# rc13-mbed-main-board2.net
KiCad netlist of a schematic drawn in EAGLE
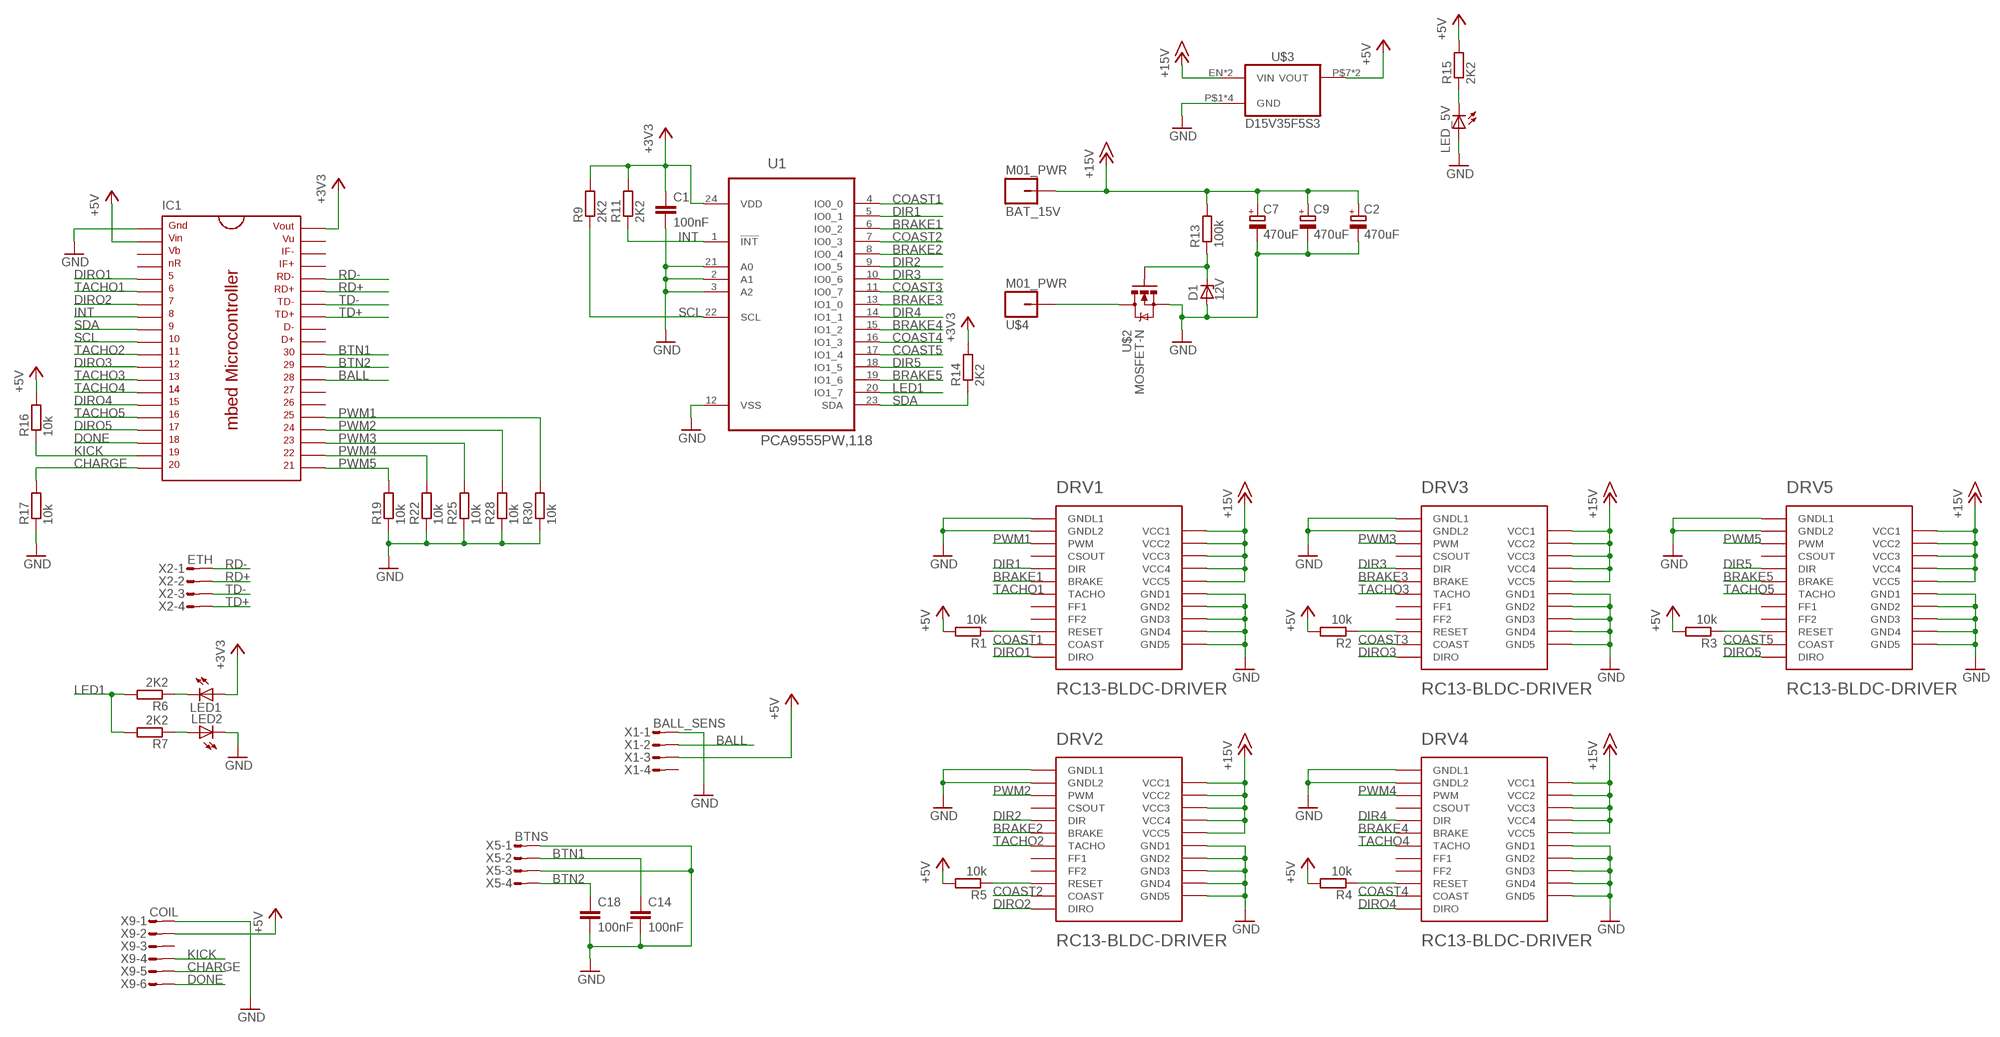
[diagram p0: schematic, sheet 1]

(export (version "E")
  (design (tool "Eeschema 10.0.6"))
  (components
    (comp (ref "BAT_15V")
      (value "M01_PWR")
      (footprint "eagle-import:PWR_HOLE")
      (libsource (lib "eagle-import") (part "M01_PWR"))
    )
    (comp (ref "C1")
      (value "100nF")
      (footprint "eagle-import:C0603K")
      (libsource (lib "eagle-import") (part "C-EUC0603K"))
    )
    (comp (ref "C2")
      (value "470uF")
      (footprint "eagle-import:E3,5-8")
      (libsource (lib "eagle-import") (part "CPOL-EUE3.5-8"))
    )
    (comp (ref "C7")
      (value "470uF")
      (footprint "eagle-import:E3,5-8")
      (libsource (lib "eagle-import") (part "CPOL-EUE3.5-8"))
    )
    (comp (ref "C9")
      (value "470uF")
      (footprint "eagle-import:E3,5-8")
      (libsource (lib "eagle-import") (part "CPOL-EUE3.5-8"))
    )
    (comp (ref "C14")
      (value "100nF")
      (footprint "eagle-import:C0603K")
      (libsource (lib "eagle-import") (part "C-EUC0603K"))
    )
    (comp (ref "C18")
      (value "100nF")
      (footprint "eagle-import:C0603K")
      (libsource (lib "eagle-import") (part "C-EUC0603K"))
    )
    (comp (ref "D1")
      (value "12V")
      (footprint "eagle-import:SOD123")
      (libsource (lib "eagle-import") (part "ZENER-DIODESOD123"))
    )
    (comp (ref "DRV1")
      (value "RC13-BLDC-DRIVER")
      (footprint "eagle-import:RC13-BLDC-DRIVER")
      (libsource (lib "eagle-import") (part "RC13-BLDC-DRIVER"))
    )
    (comp (ref "DRV2")
      (value "RC13-BLDC-DRIVER")
      (footprint "eagle-import:RC13-BLDC-DRIVER")
      (libsource (lib "eagle-import") (part "RC13-BLDC-DRIVER"))
    )
    (comp (ref "DRV3")
      (value "RC13-BLDC-DRIVER")
      (footprint "eagle-import:RC13-BLDC-DRIVER")
      (libsource (lib "eagle-import") (part "RC13-BLDC-DRIVER"))
    )
    (comp (ref "DRV4")
      (value "RC13-BLDC-DRIVER")
      (footprint "eagle-import:RC13-BLDC-DRIVER")
      (libsource (lib "eagle-import") (part "RC13-BLDC-DRIVER"))
    )
    (comp (ref "DRV5")
      (value "RC13-BLDC-DRIVER")
      (footprint "eagle-import:RC13-BLDC-DRIVER")
      (libsource (lib "eagle-import") (part "RC13-BLDC-DRIVER"))
    )
    (comp (ref "IC1")
      (value "MBED_MICROCONTROLLER")
      (footprint "eagle-import:DIL40_0.9")
      (libsource (lib "eagle-import") (part "MBED_MICROCONTROLLER"))
    )
    (comp (ref "LED1")
      (value "LEDCHIP-LED0603")
      (footprint "eagle-import:CHIP-LED0603")
      (libsource (lib "eagle-import") (part "LEDCHIP-LED0603"))
    )
    (comp (ref "LED2")
      (value "LEDCHIP-LED0603")
      (footprint "eagle-import:CHIP-LED0603")
      (libsource (lib "eagle-import") (part "LEDCHIP-LED0603"))
    )
    (comp (ref "LED_5V")
      (value "LEDCHIP-LED0603")
      (footprint "eagle-import:CHIP-LED0603")
      (libsource (lib "eagle-import") (part "LEDCHIP-LED0603"))
    )
    (comp (ref "R1")
      (value "10k")
      (footprint "eagle-import:R0603")
      (libsource (lib "eagle-import") (part "R-EU_R0603"))
    )
    (comp (ref "R2")
      (value "10k")
      (footprint "eagle-import:R0603")
      (libsource (lib "eagle-import") (part "R-EU_R0603"))
    )
    (comp (ref "R3")
      (value "10k")
      (footprint "eagle-import:R0603")
      (libsource (lib "eagle-import") (part "R-EU_R0603"))
    )
    (comp (ref "R4")
      (value "10k")
      (footprint "eagle-import:R0603")
      (libsource (lib "eagle-import") (part "R-EU_R0603"))
    )
    (comp (ref "R5")
      (value "10k")
      (footprint "eagle-import:R0603")
      (libsource (lib "eagle-import") (part "R-EU_R0603"))
    )
    (comp (ref "R6")
      (value "2K2")
      (footprint "eagle-import:R0603")
      (libsource (lib "eagle-import") (part "R-EU_R0603"))
    )
    (comp (ref "R7")
      (value "2K2")
      (footprint "eagle-import:R0603")
      (libsource (lib "eagle-import") (part "R-EU_R0603"))
    )
    (comp (ref "R9")
      (value "2K2")
      (footprint "eagle-import:R0603")
      (libsource (lib "eagle-import") (part "R-EU_R0603"))
    )
    (comp (ref "R11")
      (value "2K2")
      (footprint "eagle-import:R0603")
      (libsource (lib "eagle-import") (part "R-EU_R0603"))
    )
    (comp (ref "R13")
      (value "100k")
      (footprint "eagle-import:R0603")
      (libsource (lib "eagle-import") (part "R-EU_R0603"))
    )
    (comp (ref "R14")
      (value "2K2")
      (footprint "eagle-import:R0603")
      (libsource (lib "eagle-import") (part "R-EU_R0603"))
    )
    (comp (ref "R15")
      (value "2K2")
      (footprint "eagle-import:R0603")
      (libsource (lib "eagle-import") (part "R-EU_R0603"))
    )
    (comp (ref "R16")
      (value "10k")
      (footprint "eagle-import:R0603")
      (libsource (lib "eagle-import") (part "R-EU_R0603"))
    )
    (comp (ref "R17")
      (value "10k")
      (footprint "eagle-import:R0603")
      (libsource (lib "eagle-import") (part "R-EU_R0603"))
    )
    (comp (ref "R19")
      (value "10k")
      (footprint "eagle-import:R0603")
      (libsource (lib "eagle-import") (part "R-EU_R0603"))
    )
    (comp (ref "R22")
      (value "10k")
      (footprint "eagle-import:R0603")
      (libsource (lib "eagle-import") (part "R-EU_R0603"))
    )
    (comp (ref "R25")
      (value "10k")
      (footprint "eagle-import:R0603")
      (libsource (lib "eagle-import") (part "R-EU_R0603"))
    )
    (comp (ref "R28")
      (value "10k")
      (footprint "eagle-import:R0603")
      (libsource (lib "eagle-import") (part "R-EU_R0603"))
    )
    (comp (ref "R30")
      (value "10k")
      (footprint "eagle-import:R0603")
      (libsource (lib "eagle-import") (part "R-EU_R0603"))
    )
    (comp (ref "U$2")
      (value "MOSFET-N")
      (footprint "eagle-import:TO127P600X120-5N")
      (libsource (lib "eagle-import") (part "MOSFET-N-SOT669"))
    )
    (comp (ref "U$3")
      (value "D15V35F5S3")
      (footprint "eagle-import:D15V35F5S3")
      (libsource (lib "eagle-import") (part "D15V35F5S3"))
    )
    (comp (ref "U$4")
      (value "M01_PWR")
      (footprint "eagle-import:PWR_HOLE")
      (libsource (lib "eagle-import") (part "M01_PWR"))
    )
    (comp (ref "U1")
      (value "PCA9555PW,118")
      (footprint "eagle-import:SOP65P640X110-24N")
      (libsource (lib "eagle-import") (part "PCA9555PW,118"))
    )
    (comp (ref "X1")
      (value "BALL_SENS")
      (footprint "eagle-import:MICROMATCH-4")
      (fields (field (name "MPN") "7-215464-4"))
      (libsource (lib "eagle-import") (part "MICROMATCH-4"))
    )
    (comp (ref "X2")
      (value "ETH")
      (footprint "eagle-import:MICROMATCH-4")
      (fields (field (name "MPN") "7-215464-4"))
      (libsource (lib "eagle-import") (part "MICROMATCH-4"))
    )
    (comp (ref "X5")
      (value "BTNS")
      (footprint "eagle-import:MICROMATCH-4")
      (fields (field (name "MPN") "7-215464-4"))
      (libsource (lib "eagle-import") (part "MICROMATCH-4"))
    )
    (comp (ref "X9")
      (value "COIL")
      (footprint "eagle-import:MICROMATCH-6")
      (fields (field (name "MPN") "7-215464-6"))
      (libsource (lib "eagle-import") (part "MICROMATCH-6"))
    )
  )
  (nets
    (net (code "1") (name "+3V3") (class "Default")
      (node (ref "C1") (pin "1") (pinfunction "1_1") (pintype "passive"))
      (node (ref "IC1") (pin "40") (pinfunction "P$40_40") (pintype "bidirectional"))
      (node (ref "LED1") (pin "A") (pinfunction "A_A") (pintype "passive"))
      (node (ref "R11") (pin "2") (pinfunction "2_2") (pintype "passive"))
      (node (ref "R14") (pin "2") (pinfunction "2_2") (pintype "passive"))
      (node (ref "R9") (pin "2") (pinfunction "2_2") (pintype "passive"))
      (node (ref "U1") (pin "24") (pinfunction "VDD_24") (pintype "power_in"))
    )
    (net (code "2") (name "+5V") (class "Default")
      (node (ref "IC1") (pin "2") (pinfunction "P$2_2") (pintype "bidirectional"))
      (node (ref "R1") (pin "2") (pinfunction "2_2") (pintype "passive"))
      (node (ref "R15") (pin "2") (pinfunction "2_2") (pintype "passive"))
      (node (ref "R16") (pin "2") (pinfunction "2_2") (pintype "passive"))
      (node (ref "R2") (pin "2") (pinfunction "2_2") (pintype "passive"))
      (node (ref "R3") (pin "2") (pinfunction "2_2") (pintype "passive"))
      (node (ref "R4") (pin "2") (pinfunction "2_2") (pintype "passive"))
      (node (ref "R5") (pin "2") (pinfunction "2_2") (pintype "passive"))
      (node (ref "U$3") (pin "P$7") (pinfunction "VOUT_P$7") (pintype "power_in"))
      (node (ref "U$3") (pin "P$8") (pinfunction "VOUT_P$8") (pintype "power_in"))
      (node (ref "X1") (pin "3") (pinfunction "S_3") (pintype "passive"))
      (node (ref "X9") (pin "2") (pinfunction "S_2") (pintype "passive"))
    )
    (net (code "3") (name "+15V") (class "Default")
      (node (ref "BAT_15V") (pin "P$1") (pinfunction "P$1_P$1") (pintype "bidirectional"))
      (node (ref "C2") (pin "+") (pinfunction "+_+") (pintype "passive"))
      (node (ref "C7") (pin "+") (pinfunction "+_+") (pintype "passive"))
      (node (ref "C9") (pin "+") (pinfunction "+_+") (pintype "passive"))
      (node (ref "DRV1") (pin "PWR1") (pinfunction "VCC1_PWR1") (pintype "power_in"))
      (node (ref "DRV1") (pin "PWR2") (pinfunction "VCC2_PWR2") (pintype "power_in"))
      (node (ref "DRV1") (pin "PWR3") (pinfunction "VCC3_PWR3") (pintype "power_in"))
      (node (ref "DRV1") (pin "PWR4") (pinfunction "VCC4_PWR4") (pintype "power_in"))
      (node (ref "DRV1") (pin "PWR5") (pinfunction "VCC5_PWR5") (pintype "power_in"))
      (node (ref "DRV2") (pin "PWR1") (pinfunction "VCC1_PWR1") (pintype "power_in"))
      (node (ref "DRV2") (pin "PWR2") (pinfunction "VCC2_PWR2") (pintype "power_in"))
      (node (ref "DRV2") (pin "PWR3") (pinfunction "VCC3_PWR3") (pintype "power_in"))
      (node (ref "DRV2") (pin "PWR4") (pinfunction "VCC4_PWR4") (pintype "power_in"))
      (node (ref "DRV2") (pin "PWR5") (pinfunction "VCC5_PWR5") (pintype "power_in"))
      (node (ref "DRV3") (pin "PWR1") (pinfunction "VCC1_PWR1") (pintype "power_in"))
      (node (ref "DRV3") (pin "PWR2") (pinfunction "VCC2_PWR2") (pintype "power_in"))
      (node (ref "DRV3") (pin "PWR3") (pinfunction "VCC3_PWR3") (pintype "power_in"))
      (node (ref "DRV3") (pin "PWR4") (pinfunction "VCC4_PWR4") (pintype "power_in"))
      (node (ref "DRV3") (pin "PWR5") (pinfunction "VCC5_PWR5") (pintype "power_in"))
      (node (ref "DRV4") (pin "PWR1") (pinfunction "VCC1_PWR1") (pintype "power_in"))
      (node (ref "DRV4") (pin "PWR2") (pinfunction "VCC2_PWR2") (pintype "power_in"))
      (node (ref "DRV4") (pin "PWR3") (pinfunction "VCC3_PWR3") (pintype "power_in"))
      (node (ref "DRV4") (pin "PWR4") (pinfunction "VCC4_PWR4") (pintype "power_in"))
      (node (ref "DRV4") (pin "PWR5") (pinfunction "VCC5_PWR5") (pintype "power_in"))
      (node (ref "DRV5") (pin "PWR1") (pinfunction "VCC1_PWR1") (pintype "power_in"))
      (node (ref "DRV5") (pin "PWR2") (pinfunction "VCC2_PWR2") (pintype "power_in"))
      (node (ref "DRV5") (pin "PWR3") (pinfunction "VCC3_PWR3") (pintype "power_in"))
      (node (ref "DRV5") (pin "PWR4") (pinfunction "VCC4_PWR4") (pintype "power_in"))
      (node (ref "DRV5") (pin "PWR5") (pinfunction "VCC5_PWR5") (pintype "power_in"))
      (node (ref "R13") (pin "2") (pinfunction "2_2") (pintype "passive"))
      (node (ref "U$3") (pin "EN") (pinfunction "VIN_EN") (pintype "power_in"))
      (node (ref "U$3") (pin "P$5") (pinfunction "VIN_P$5") (pintype "power_in"))
    )
    (net (code "4") (name "/BALL") (class "Default")
      (node (ref "IC1") (pin "28") (pinfunction "P$28_28") (pintype "bidirectional"))
      (node (ref "X1") (pin "2") (pinfunction "S_2") (pintype "passive"))
    )
    (net (code "5") (name "/BRAKE1") (class "Default")
      (node (ref "DRV1") (pin "LOGIC6") (pinfunction "BRAKE_LOGIC6") (pintype "input"))
      (node (ref "U1") (pin "6") (pinfunction "IO0_2_6") (pintype "bidirectional"))
    )
    (net (code "6") (name "/BRAKE2") (class "Default")
      (node (ref "DRV2") (pin "LOGIC6") (pinfunction "BRAKE_LOGIC6") (pintype "input"))
      (node (ref "U1") (pin "8") (pinfunction "IO0_4_8") (pintype "bidirectional"))
    )
    (net (code "7") (name "/BRAKE3") (class "Default")
      (node (ref "DRV3") (pin "LOGIC6") (pinfunction "BRAKE_LOGIC6") (pintype "input"))
      (node (ref "U1") (pin "13") (pinfunction "IO1_0_13") (pintype "bidirectional"))
    )
    (net (code "8") (name "/BRAKE4") (class "Default")
      (node (ref "DRV4") (pin "LOGIC6") (pinfunction "BRAKE_LOGIC6") (pintype "input"))
      (node (ref "U1") (pin "15") (pinfunction "IO1_2_15") (pintype "bidirectional"))
    )
    (net (code "9") (name "/BRAKE5") (class "Default")
      (node (ref "DRV5") (pin "LOGIC6") (pinfunction "BRAKE_LOGIC6") (pintype "input"))
      (node (ref "U1") (pin "19") (pinfunction "IO1_6_19") (pintype "bidirectional"))
    )
    (net (code "10") (name "/BTN1") (class "Default")
      (node (ref "C14") (pin "1") (pinfunction "1_1") (pintype "passive"))
      (node (ref "IC1") (pin "30") (pinfunction "P$30_30") (pintype "bidirectional"))
      (node (ref "X5") (pin "2") (pinfunction "S_2") (pintype "passive"))
    )
    (net (code "11") (name "/BTN2") (class "Default")
      (node (ref "C18") (pin "1") (pinfunction "1_1") (pintype "passive"))
      (node (ref "IC1") (pin "29") (pinfunction "P$29_29") (pintype "bidirectional"))
      (node (ref "X5") (pin "4") (pinfunction "S_4") (pintype "passive"))
    )
    (net (code "12") (name "/CHARGE") (class "Default")
      (node (ref "IC1") (pin "20") (pinfunction "P$20_20") (pintype "bidirectional"))
      (node (ref "R17") (pin "2") (pinfunction "2_2") (pintype "passive"))
      (node (ref "X9") (pin "5") (pinfunction "S_5") (pintype "passive"))
    )
    (net (code "13") (name "/COAST1") (class "Default")
      (node (ref "DRV1") (pin "LOGIC11") (pinfunction "COAST_LOGIC11") (pintype "input"))
      (node (ref "U1") (pin "4") (pinfunction "IO0_0_4") (pintype "bidirectional"))
    )
    (net (code "14") (name "/COAST2") (class "Default")
      (node (ref "DRV2") (pin "LOGIC11") (pinfunction "COAST_LOGIC11") (pintype "input"))
      (node (ref "U1") (pin "7") (pinfunction "IO0_3_7") (pintype "bidirectional"))
    )
    (net (code "15") (name "/COAST3") (class "Default")
      (node (ref "DRV3") (pin "LOGIC11") (pinfunction "COAST_LOGIC11") (pintype "input"))
      (node (ref "U1") (pin "11") (pinfunction "IO0_7_11") (pintype "bidirectional"))
    )
    (net (code "16") (name "/COAST4") (class "Default")
      (node (ref "DRV4") (pin "LOGIC11") (pinfunction "COAST_LOGIC11") (pintype "input"))
      (node (ref "U1") (pin "16") (pinfunction "IO1_3_16") (pintype "bidirectional"))
    )
    (net (code "17") (name "/COAST5") (class "Default")
      (node (ref "DRV5") (pin "LOGIC11") (pinfunction "COAST_LOGIC11") (pintype "input"))
      (node (ref "U1") (pin "17") (pinfunction "IO1_4_17") (pintype "bidirectional"))
    )
    (net (code "18") (name "/DIR1") (class "Default")
      (node (ref "DRV1") (pin "LOGIC5") (pinfunction "DIR_LOGIC5") (pintype "input"))
      (node (ref "U1") (pin "5") (pinfunction "IO0_1_5") (pintype "bidirectional"))
    )
    (net (code "19") (name "/DIR2") (class "Default")
      (node (ref "DRV2") (pin "LOGIC5") (pinfunction "DIR_LOGIC5") (pintype "input"))
      (node (ref "U1") (pin "9") (pinfunction "IO0_5_9") (pintype "bidirectional"))
    )
    (net (code "20") (name "/DIR3") (class "Default")
      (node (ref "DRV3") (pin "LOGIC5") (pinfunction "DIR_LOGIC5") (pintype "input"))
      (node (ref "U1") (pin "10") (pinfunction "IO0_6_10") (pintype "bidirectional"))
    )
    (net (code "21") (name "/DIR4") (class "Default")
      (node (ref "DRV4") (pin "LOGIC5") (pinfunction "DIR_LOGIC5") (pintype "input"))
      (node (ref "U1") (pin "14") (pinfunction "IO1_1_14") (pintype "bidirectional"))
    )
    (net (code "22") (name "/DIR5") (class "Default")
      (node (ref "DRV5") (pin "LOGIC5") (pinfunction "DIR_LOGIC5") (pintype "input"))
      (node (ref "U1") (pin "18") (pinfunction "IO1_5_18") (pintype "bidirectional"))
    )
    (net (code "23") (name "/DIRO1") (class "Default")
      (node (ref "DRV1") (pin "LOGIC12") (pinfunction "DIRO_LOGIC12") (pintype "output"))
      (node (ref "IC1") (pin "5") (pinfunction "P$5_5") (pintype "bidirectional"))
    )
    (net (code "24") (name "/DIRO2") (class "Default")
      (node (ref "DRV2") (pin "LOGIC12") (pinfunction "DIRO_LOGIC12") (pintype "output"))
      (node (ref "IC1") (pin "7") (pinfunction "P$7_7") (pintype "bidirectional"))
    )
    (net (code "25") (name "/DIRO3") (class "Default")
      (node (ref "DRV3") (pin "LOGIC12") (pinfunction "DIRO_LOGIC12") (pintype "output"))
      (node (ref "IC1") (pin "12") (pinfunction "P$12_12") (pintype "bidirectional"))
    )
    (net (code "26") (name "/DIRO4") (class "Default")
      (node (ref "DRV4") (pin "LOGIC12") (pinfunction "DIRO_LOGIC12") (pintype "output"))
      (node (ref "IC1") (pin "15") (pinfunction "P$15_15") (pintype "bidirectional"))
    )
    (net (code "27") (name "/DIRO5") (class "Default")
      (node (ref "DRV5") (pin "LOGIC12") (pinfunction "DIRO_LOGIC12") (pintype "output"))
      (node (ref "IC1") (pin "17") (pinfunction "P$17_17") (pintype "bidirectional"))
    )
    (net (code "28") (name "/DONE") (class "Default")
      (node (ref "IC1") (pin "18") (pinfunction "P$18_18") (pintype "bidirectional"))
      (node (ref "X9") (pin "6") (pinfunction "S_6") (pintype "passive"))
    )
    (net (code "29") (name "/INT") (class "Default")
      (node (ref "IC1") (pin "8") (pinfunction "P$8_8") (pintype "bidirectional"))
      (node (ref "R11") (pin "1") (pinfunction "1_1") (pintype "passive"))
      (node (ref "U1") (pin "1") (pinfunction "~{INT}_1") (pintype "output"))
    )
    (net (code "30") (name "/KICK") (class "Default")
      (node (ref "IC1") (pin "19") (pinfunction "P$19_19") (pintype "bidirectional"))
      (node (ref "R16") (pin "1") (pinfunction "1_1") (pintype "passive"))
      (node (ref "X9") (pin "4") (pinfunction "S_4") (pintype "passive"))
    )
    (net (code "31") (name "/LED1") (class "Default")
      (node (ref "R6") (pin "2") (pinfunction "2_2") (pintype "passive"))
      (node (ref "R7") (pin "2") (pinfunction "2_2") (pintype "passive"))
      (node (ref "U1") (pin "20") (pinfunction "IO1_7_20") (pintype "bidirectional"))
    )
    (net (code "32") (name "/PWM1") (class "Default")
      (node (ref "DRV1") (pin "LOGIC3") (pinfunction "PWM_LOGIC3") (pintype "input"))
      (node (ref "IC1") (pin "25") (pinfunction "P$25_25") (pintype "bidirectional"))
      (node (ref "R30") (pin "2") (pinfunction "2_2") (pintype "passive"))
    )
    (net (code "33") (name "/PWM2") (class "Default")
      (node (ref "DRV2") (pin "LOGIC3") (pinfunction "PWM_LOGIC3") (pintype "input"))
      (node (ref "IC1") (pin "24") (pinfunction "P$24_24") (pintype "bidirectional"))
      (node (ref "R28") (pin "2") (pinfunction "2_2") (pintype "passive"))
    )
    (net (code "34") (name "/PWM3") (class "Default")
      (node (ref "DRV3") (pin "LOGIC3") (pinfunction "PWM_LOGIC3") (pintype "input"))
      (node (ref "IC1") (pin "23") (pinfunction "P$23_23") (pintype "bidirectional"))
      (node (ref "R25") (pin "2") (pinfunction "2_2") (pintype "passive"))
    )
    (net (code "35") (name "/PWM4") (class "Default")
      (node (ref "DRV4") (pin "LOGIC3") (pinfunction "PWM_LOGIC3") (pintype "input"))
      (node (ref "IC1") (pin "22") (pinfunction "P$22_22") (pintype "bidirectional"))
      (node (ref "R22") (pin "2") (pinfunction "2_2") (pintype "passive"))
    )
    (net (code "36") (name "/PWM5") (class "Default")
      (node (ref "DRV5") (pin "LOGIC3") (pinfunction "PWM_LOGIC3") (pintype "input"))
      (node (ref "IC1") (pin "21") (pinfunction "P$21_21") (pintype "bidirectional"))
      (node (ref "R19") (pin "2") (pinfunction "2_2") (pintype "passive"))
    )
    (net (code "37") (name "/RD+") (class "Default")
      (node (ref "IC1") (pin "35") (pinfunction "P$35_35") (pintype "bidirectional"))
      (node (ref "X2") (pin "2") (pinfunction "S_2") (pintype "passive"))
    )
    (net (code "38") (name "/RD-") (class "Default")
      (node (ref "IC1") (pin "36") (pinfunction "P$36_36") (pintype "bidirectional"))
      (node (ref "X2") (pin "1") (pinfunction "S_1") (pintype "passive"))
    )
    (net (code "39") (name "/SCL") (class "Default")
      (node (ref "IC1") (pin "10") (pinfunction "P$10_10") (pintype "bidirectional"))
      (node (ref "R9") (pin "1") (pinfunction "1_1") (pintype "passive"))
      (node (ref "U1") (pin "22") (pinfunction "SCL_22") (pintype "input"))
    )
    (net (code "40") (name "/SDA") (class "Default")
      (node (ref "IC1") (pin "9") (pinfunction "P$9_9") (pintype "bidirectional"))
      (node (ref "R14") (pin "1") (pinfunction "1_1") (pintype "passive"))
      (node (ref "U1") (pin "23") (pinfunction "SDA_23") (pintype "bidirectional"))
    )
    (net (code "41") (name "/TACHO1") (class "Default")
      (node (ref "DRV1") (pin "LOGIC7") (pinfunction "TACHO_LOGIC7") (pintype "output"))
      (node (ref "IC1") (pin "6") (pinfunction "P$6_6") (pintype "bidirectional"))
    )
    (net (code "42") (name "/TACHO2") (class "Default")
      (node (ref "DRV2") (pin "LOGIC7") (pinfunction "TACHO_LOGIC7") (pintype "output"))
      (node (ref "IC1") (pin "11") (pinfunction "P$11_11") (pintype "bidirectional"))
    )
    (net (code "43") (name "/TACHO3") (class "Default")
      (node (ref "DRV3") (pin "LOGIC7") (pinfunction "TACHO_LOGIC7") (pintype "output"))
      (node (ref "IC1") (pin "13") (pinfunction "P$13_13") (pintype "bidirectional"))
    )
    (net (code "44") (name "/TACHO4") (class "Default")
      (node (ref "DRV4") (pin "LOGIC7") (pinfunction "TACHO_LOGIC7") (pintype "output"))
      (node (ref "IC1") (pin "14") (pinfunction "P$14_14") (pintype "bidirectional"))
    )
    (net (code "45") (name "/TACHO5") (class "Default")
      (node (ref "DRV5") (pin "LOGIC7") (pinfunction "TACHO_LOGIC7") (pintype "output"))
      (node (ref "IC1") (pin "16") (pinfunction "P$16_16") (pintype "bidirectional"))
    )
    (net (code "46") (name "/TD+") (class "Default")
      (node (ref "IC1") (pin "33") (pinfunction "P$33_33") (pintype "bidirectional"))
      (node (ref "X2") (pin "4") (pinfunction "S_4") (pintype "passive"))
    )
    (net (code "47") (name "/TD-") (class "Default")
      (node (ref "IC1") (pin "34") (pinfunction "P$34_34") (pintype "bidirectional"))
      (node (ref "X2") (pin "3") (pinfunction "S_3") (pintype "passive"))
    )
    (net (code "48") (name "GND") (class "Default")
      (node (ref "C1") (pin "2") (pinfunction "2_2") (pintype "passive"))
      (node (ref "C14") (pin "2") (pinfunction "2_2") (pintype "passive"))
      (node (ref "C18") (pin "2") (pinfunction "2_2") (pintype "passive"))
      (node (ref "C2") (pin "-") (pinfunction "-_-") (pintype "passive"))
      (node (ref "C7") (pin "-") (pinfunction "-_-") (pintype "passive"))
      (node (ref "C9") (pin "-") (pinfunction "-_-") (pintype "passive"))
      (node (ref "D1") (pin "A") (pinfunction "A_A") (pintype "passive"))
      (node (ref "DRV1") (pin "LOGIC1") (pinfunction "GNDL1_LOGIC1") (pintype "power_in"))
      (node (ref "DRV1") (pin "LOGIC2") (pinfunction "GNDL2_LOGIC2") (pintype "power_in"))
      (node (ref "DRV1") (pin "PWR10") (pinfunction "GND5_PWR10") (pintype "power_in"))
      (node (ref "DRV1") (pin "PWR6") (pinfunction "GND1_PWR6") (pintype "power_in"))
      (node (ref "DRV1") (pin "PWR7") (pinfunction "GND2_PWR7") (pintype "power_in"))
      (node (ref "DRV1") (pin "PWR8") (pinfunction "GND3_PWR8") (pintype "power_in"))
      (node (ref "DRV1") (pin "PWR9") (pinfunction "GND4_PWR9") (pintype "power_in"))
      (node (ref "DRV2") (pin "LOGIC1") (pinfunction "GNDL1_LOGIC1") (pintype "power_in"))
      (node (ref "DRV2") (pin "LOGIC2") (pinfunction "GNDL2_LOGIC2") (pintype "power_in"))
      (node (ref "DRV2") (pin "PWR10") (pinfunction "GND5_PWR10") (pintype "power_in"))
      (node (ref "DRV2") (pin "PWR6") (pinfunction "GND1_PWR6") (pintype "power_in"))
      (node (ref "DRV2") (pin "PWR7") (pinfunction "GND2_PWR7") (pintype "power_in"))
      (node (ref "DRV2") (pin "PWR8") (pinfunction "GND3_PWR8") (pintype "power_in"))
      (node (ref "DRV2") (pin "PWR9") (pinfunction "GND4_PWR9") (pintype "power_in"))
      (node (ref "DRV3") (pin "LOGIC1") (pinfunction "GNDL1_LOGIC1") (pintype "power_in"))
      (node (ref "DRV3") (pin "LOGIC2") (pinfunction "GNDL2_LOGIC2") (pintype "power_in"))
      (node (ref "DRV3") (pin "PWR10") (pinfunction "GND5_PWR10") (pintype "power_in"))
      (node (ref "DRV3") (pin "PWR6") (pinfunction "GND1_PWR6") (pintype "power_in"))
      (node (ref "DRV3") (pin "PWR7") (pinfunction "GND2_PWR7") (pintype "power_in"))
      (node (ref "DRV3") (pin "PWR8") (pinfunction "GND3_PWR8") (pintype "power_in"))
      (node (ref "DRV3") (pin "PWR9") (pinfunction "GND4_PWR9") (pintype "power_in"))
      (node (ref "DRV4") (pin "LOGIC1") (pinfunction "GNDL1_LOGIC1") (pintype "power_in"))
      (node (ref "DRV4") (pin "LOGIC2") (pinfunction "GNDL2_LOGIC2") (pintype "power_in"))
      (node (ref "DRV4") (pin "PWR10") (pinfunction "GND5_PWR10") (pintype "power_in"))
      (node (ref "DRV4") (pin "PWR6") (pinfunction "GND1_PWR6") (pintype "power_in"))
      (node (ref "DRV4") (pin "PWR7") (pinfunction "GND2_PWR7") (pintype "power_in"))
      (node (ref "DRV4") (pin "PWR8") (pinfunction "GND3_PWR8") (pintype "power_in"))
      (node (ref "DRV4") (pin "PWR9") (pinfunction "GND4_PWR9") (pintype "power_in"))
      (node (ref "DRV5") (pin "LOGIC1") (pinfunction "GNDL1_LOGIC1") (pintype "power_in"))
      (node (ref "DRV5") (pin "LOGIC2") (pinfunction "GNDL2_LOGIC2") (pintype "power_in"))
      (node (ref "DRV5") (pin "PWR10") (pinfunction "GND5_PWR10") (pintype "power_in"))
      (node (ref "DRV5") (pin "PWR6") (pinfunction "GND1_PWR6") (pintype "power_in"))
      (node (ref "DRV5") (pin "PWR7") (pinfunction "GND2_PWR7") (pintype "power_in"))
      (node (ref "DRV5") (pin "PWR8") (pinfunction "GND3_PWR8") (pintype "power_in"))
      (node (ref "DRV5") (pin "PWR9") (pinfunction "GND4_PWR9") (pintype "power_in"))
      (node (ref "IC1") (pin "1") (pinfunction "P$1_1") (pintype "bidirectional"))
      (node (ref "LED2") (pin "C") (pinfunction "C_C") (pintype "passive"))
      (node (ref "LED_5V") (pin "A") (pinfunction "A_A") (pintype "passive"))
      (node (ref "R17") (pin "1") (pinfunction "1_1") (pintype "passive"))
      (node (ref "R19") (pin "1") (pinfunction "1_1") (pintype "passive"))
      (node (ref "R22") (pin "1") (pinfunction "1_1") (pintype "passive"))
      (node (ref "R25") (pin "1") (pinfunction "1_1") (pintype "passive"))
      (node (ref "R28") (pin "1") (pinfunction "1_1") (pintype "passive"))
      (node (ref "R30") (pin "1") (pinfunction "1_1") (pintype "passive"))
      (node (ref "U$2") (pin "1") (pinfunction "S_1") (pintype "passive"))
      (node (ref "U$2") (pin "2") (pinfunction "S_2") (pintype "passive"))
      (node (ref "U$2") (pin "3") (pinfunction "S_3") (pintype "passive"))
      (node (ref "U$3") (pin "P$1") (pinfunction "GND_P$1") (pintype "power_in"))
      (node (ref "U$3") (pin "P$2") (pinfunction "GND_P$2") (pintype "power_in"))
      (node (ref "U$3") (pin "P$3") (pinfunction "GND_P$3") (pintype "power_in"))
      (node (ref "U$3") (pin "P$4") (pinfunction "GND_P$4") (pintype "power_in"))
      (node (ref "U1") (pin "12") (pinfunction "VSS_12") (pintype "power_in"))
      (node (ref "U1") (pin "2") (pinfunction "A1_2") (pintype "input"))
      (node (ref "U1") (pin "21") (pinfunction "A0_21") (pintype "input"))
      (node (ref "U1") (pin "3") (pinfunction "A2_3") (pintype "input"))
      (node (ref "X1") (pin "1") (pinfunction "S_1") (pintype "passive"))
      (node (ref "X5") (pin "1") (pinfunction "S_1") (pintype "passive"))
      (node (ref "X5") (pin "3") (pinfunction "S_3") (pintype "passive"))
      (node (ref "X9") (pin "1") (pinfunction "S_1") (pintype "passive"))
    )
    (net (code "49") (name "Net-(DRV1-RESET)") (class "Default")
      (node (ref "DRV1") (pin "LOGIC10") (pinfunction "RESET_LOGIC10") (pintype "input"))
      (node (ref "R1") (pin "1") (pinfunction "1_1") (pintype "passive"))
    )
    (net (code "50") (name "Net-(DRV2-RESET)") (class "Default")
      (node (ref "DRV2") (pin "LOGIC10") (pinfunction "RESET_LOGIC10") (pintype "input"))
      (node (ref "R5") (pin "1") (pinfunction "1_1") (pintype "passive"))
    )
    (net (code "51") (name "Net-(DRV3-RESET)") (class "Default")
      (node (ref "DRV3") (pin "LOGIC10") (pinfunction "RESET_LOGIC10") (pintype "input"))
      (node (ref "R2") (pin "1") (pinfunction "1_1") (pintype "passive"))
    )
    (net (code "52") (name "Net-(DRV4-RESET)") (class "Default")
      (node (ref "DRV4") (pin "LOGIC10") (pinfunction "RESET_LOGIC10") (pintype "input"))
      (node (ref "R4") (pin "1") (pinfunction "1_1") (pintype "passive"))
    )
    (net (code "53") (name "Net-(DRV5-RESET)") (class "Default")
      (node (ref "DRV5") (pin "LOGIC10") (pinfunction "RESET_LOGIC10") (pintype "input"))
      (node (ref "R3") (pin "1") (pinfunction "1_1") (pintype "passive"))
    )
    (net (code "54") (name "Net-(LED1-PadC)") (class "Default")
      (node (ref "LED1") (pin "C") (pinfunction "C_C") (pintype "passive"))
      (node (ref "R6") (pin "1") (pinfunction "1_1") (pintype "passive"))
    )
    (net (code "55") (name "Net-(LED2-PadA)") (class "Default")
      (node (ref "LED2") (pin "A") (pinfunction "A_A") (pintype "passive"))
      (node (ref "R7") (pin "1") (pinfunction "1_1") (pintype "passive"))
    )
    (net (code "56") (name "Net-(LED_5V-PadC)") (class "Default")
      (node (ref "LED_5V") (pin "C") (pinfunction "C_C") (pintype "passive"))
      (node (ref "R15") (pin "1") (pinfunction "1_1") (pintype "passive"))
    )
    (net (code "57") (name "Net-(U$2-D)") (class "Default")
      (node (ref "U$2") (pin "5") (pinfunction "D_5") (pintype "passive"))
      (node (ref "U$4") (pin "P$1") (pinfunction "P$1_P$1") (pintype "bidirectional"))
    )
    (net (code "58") (name "Net-(U$2-G)") (class "Default")
      (node (ref "D1") (pin "C") (pinfunction "C_C") (pintype "passive"))
      (node (ref "R13") (pin "1") (pinfunction "1_1") (pintype "passive"))
      (node (ref "U$2") (pin "4") (pinfunction "G_4") (pintype "passive"))
    )
    (net (code "59") (name "unconnected-(DRV1-CSOUT-PadLOGIC4)") (class "Default")
      (node (ref "DRV1") (pin "LOGIC4") (pinfunction "CSOUT_LOGIC4") (pintype "output"))
    )
    (net (code "60") (name "unconnected-(DRV1-FF1-PadLOGIC8)") (class "Default")
      (node (ref "DRV1") (pin "LOGIC8") (pinfunction "FF1_LOGIC8") (pintype "output"))
    )
    (net (code "61") (name "unconnected-(DRV1-FF2-PadLOGIC9)") (class "Default")
      (node (ref "DRV1") (pin "LOGIC9") (pinfunction "FF2_LOGIC9") (pintype "output"))
    )
    (net (code "62") (name "unconnected-(DRV2-CSOUT-PadLOGIC4)") (class "Default")
      (node (ref "DRV2") (pin "LOGIC4") (pinfunction "CSOUT_LOGIC4") (pintype "output"))
    )
    (net (code "63") (name "unconnected-(DRV2-FF1-PadLOGIC8)") (class "Default")
      (node (ref "DRV2") (pin "LOGIC8") (pinfunction "FF1_LOGIC8") (pintype "output"))
    )
    (net (code "64") (name "unconnected-(DRV2-FF2-PadLOGIC9)") (class "Default")
      (node (ref "DRV2") (pin "LOGIC9") (pinfunction "FF2_LOGIC9") (pintype "output"))
    )
    (net (code "65") (name "unconnected-(DRV3-CSOUT-PadLOGIC4)") (class "Default")
      (node (ref "DRV3") (pin "LOGIC4") (pinfunction "CSOUT_LOGIC4") (pintype "output"))
    )
    (net (code "66") (name "unconnected-(DRV3-FF1-PadLOGIC8)") (class "Default")
      (node (ref "DRV3") (pin "LOGIC8") (pinfunction "FF1_LOGIC8") (pintype "output"))
    )
    (net (code "67") (name "unconnected-(DRV3-FF2-PadLOGIC9)") (class "Default")
      (node (ref "DRV3") (pin "LOGIC9") (pinfunction "FF2_LOGIC9") (pintype "output"))
    )
    (net (code "68") (name "unconnected-(DRV4-CSOUT-PadLOGIC4)") (class "Default")
      (node (ref "DRV4") (pin "LOGIC4") (pinfunction "CSOUT_LOGIC4") (pintype "output"))
    )
    (net (code "69") (name "unconnected-(DRV4-FF1-PadLOGIC8)") (class "Default")
      (node (ref "DRV4") (pin "LOGIC8") (pinfunction "FF1_LOGIC8") (pintype "output"))
    )
    (net (code "70") (name "unconnected-(DRV4-FF2-PadLOGIC9)") (class "Default")
      (node (ref "DRV4") (pin "LOGIC9") (pinfunction "FF2_LOGIC9") (pintype "output"))
    )
    (net (code "71") (name "unconnected-(DRV5-CSOUT-PadLOGIC4)") (class "Default")
      (node (ref "DRV5") (pin "LOGIC4") (pinfunction "CSOUT_LOGIC4") (pintype "output"))
    )
    (net (code "72") (name "unconnected-(DRV5-FF1-PadLOGIC8)") (class "Default")
      (node (ref "DRV5") (pin "LOGIC8") (pinfunction "FF1_LOGIC8") (pintype "output"))
    )
    (net (code "73") (name "unconnected-(DRV5-FF2-PadLOGIC9)") (class "Default")
      (node (ref "DRV5") (pin "LOGIC9") (pinfunction "FF2_LOGIC9") (pintype "output"))
    )
    (net (code "74") (name "unconnected-(IC1-P$3-Pad3)") (class "Default")
      (node (ref "IC1") (pin "3") (pinfunction "P$3_3") (pintype "bidirectional"))
    )
    (net (code "75") (name "unconnected-(IC1-P$4-Pad4)") (class "Default")
      (node (ref "IC1") (pin "4") (pinfunction "P$4_4") (pintype "bidirectional"))
    )
    (net (code "76") (name "unconnected-(IC1-P$26-Pad26)") (class "Default")
      (node (ref "IC1") (pin "26") (pinfunction "P$26_26") (pintype "bidirectional"))
    )
    (net (code "77") (name "unconnected-(IC1-P$27-Pad27)") (class "Default")
      (node (ref "IC1") (pin "27") (pinfunction "P$27_27") (pintype "bidirectional"))
    )
    (net (code "78") (name "unconnected-(IC1-P$31-Pad31)") (class "Default")
      (node (ref "IC1") (pin "31") (pinfunction "P$31_31") (pintype "bidirectional"))
    )
    (net (code "79") (name "unconnected-(IC1-P$32-Pad32)") (class "Default")
      (node (ref "IC1") (pin "32") (pinfunction "P$32_32") (pintype "bidirectional"))
    )
    (net (code "80") (name "unconnected-(IC1-P$37-Pad37)") (class "Default")
      (node (ref "IC1") (pin "37") (pinfunction "P$37_37") (pintype "bidirectional"))
    )
    (net (code "81") (name "unconnected-(IC1-P$38-Pad38)") (class "Default")
      (node (ref "IC1") (pin "38") (pinfunction "P$38_38") (pintype "bidirectional"))
    )
    (net (code "82") (name "unconnected-(IC1-P$39-Pad39)") (class "Default")
      (node (ref "IC1") (pin "39") (pinfunction "P$39_39") (pintype "bidirectional"))
    )
    (net (code "83") (name "unconnected-(X1D-S-Pad4)") (class "Default")
      (node (ref "X1") (pin "4") (pinfunction "S_4") (pintype "passive"))
    )
    (net (code "84") (name "unconnected-(X9C-S-Pad3)") (class "Default")
      (node (ref "X9") (pin "3") (pinfunction "S_3") (pintype "passive"))
    )
  )
)
